# circuit.net
KiCad netlist of a schematic drawn in Altium Designer
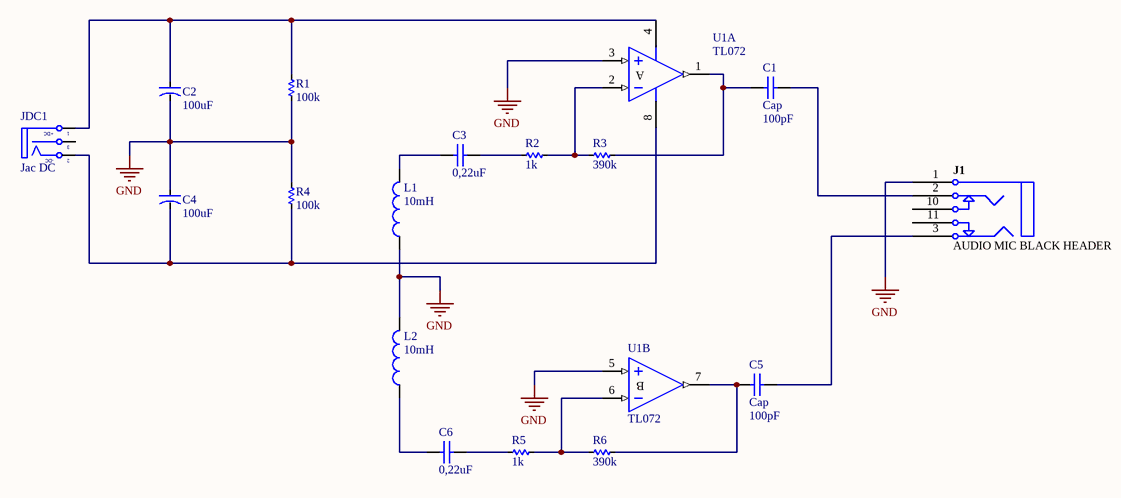
[diagram p0: circuit.schdoc]

(export (version "E")
  (design (tool "Eeschema 10.0.6"))
  (components
    (comp (ref "C1")
      (value "Cap")
      (footprint "RAD-0.3")
      (description "Capacitor")
      (fields (field (name "ALTIUM_VALUE") "100pF") (field (name "PUBLISHER") "Altium Limited"))
      (libsource (lib "Miscellaneous Devices") (part "Cap"))
    )
    (comp (ref "C2")
      (value "100uF")
      (footprint "CA-ALU-2.54")
      (description "Capacitor (Semiconductor SIM Model)")
      (fields (field (name "PUBLISHER") "Altium Limited"))
      (libsource (lib "Altium Library") (part "CN-ALU-DIP"))
    )
    (comp (ref "C3")
      (value "0,22uF")
      (footprint "RAD-0.3")
      (description "Capacitor")
      (fields (field (name "PUBLISHER") "Altium Limited"))
      (libsource (lib "Miscellaneous Devices") (part "Cap"))
    )
    (comp (ref "C4")
      (value "100uF")
      (footprint "CA-ALU-2.54")
      (description "Capacitor (Semiconductor SIM Model)")
      (fields (field (name "PUBLISHER") "Altium Limited"))
      (libsource (lib "Altium Library") (part "CN-ALU-DIP"))
    )
    (comp (ref "C5")
      (value "Cap")
      (footprint "RAD-0.3")
      (description "Capacitor")
      (fields (field (name "ALTIUM_VALUE") "100pF") (field (name "PUBLISHER") "Altium Limited"))
      (libsource (lib "Miscellaneous Devices") (part "Cap"))
    )
    (comp (ref "C6")
      (value "0,22uF")
      (footprint "RAD-0.3")
      (description "Capacitor")
      (fields (field (name "PUBLISHER") "Altium Limited"))
      (libsource (lib "Miscellaneous Devices") (part "Cap"))
    )
    (comp (ref "J1")
      (value "AUDIO MIC BLACK HEADER")
      (footprint "CON MIC1")
      (libsource (lib "Altium Library") (part "CON MIC1"))
    )
    (comp (ref "JDC1")
      (value "Jac DC")
      (footprint "DC0")
      (description "Jac DC input")
      (libsource (lib "Altium Library") (part "DCIN"))
    )
    (comp (ref "L1")
      (value "10mH")
      (footprint "0402-A")
      (description "Inductor")
      (fields (field (name "PUBLISHER") "Altium Limited"))
      (libsource (lib "Miscellaneous Devices") (part "Inductor"))
    )
    (comp (ref "L2")
      (value "10mH")
      (footprint "0402-A")
      (description "Inductor")
      (fields (field (name "PUBLISHER") "Altium Limited"))
      (libsource (lib "Miscellaneous Devices") (part "Inductor"))
    )
    (comp (ref "R1")
      (value "100k")
      (footprint "RES-1/4WD")
      (description "Res")
      (fields
        (field (name "MANUFACTURER") "Generic Components")
        (field (name "PUBLISHER") "Altium Hobart Technology Centre")
      )
      (libsource (lib "Altium Library") (part "Res"))
    )
    (comp (ref "R2")
      (value "1k")
      (footprint "RES-1/4WD")
      (description "Res")
      (fields
        (field (name "MANUFACTURER") "Generic Components")
        (field (name "PUBLISHER") "Altium Hobart Technology Centre")
      )
      (libsource (lib "Altium Library") (part "Res"))
    )
    (comp (ref "R3")
      (value "390k")
      (footprint "RES-1/4WD")
      (description "Res")
      (fields
        (field (name "MANUFACTURER") "Generic Components")
        (field (name "PUBLISHER") "Altium Hobart Technology Centre")
      )
      (libsource (lib "Altium Library") (part "Res"))
    )
    (comp (ref "R4")
      (value "100k")
      (footprint "RES-1/4WD")
      (description "Res")
      (fields
        (field (name "MANUFACTURER") "Generic Components")
        (field (name "PUBLISHER") "Altium Hobart Technology Centre")
      )
      (libsource (lib "Altium Library") (part "Res"))
    )
    (comp (ref "R5")
      (value "1k")
      (footprint "RES-1/4WD")
      (description "Res")
      (fields
        (field (name "MANUFACTURER") "Generic Components")
        (field (name "PUBLISHER") "Altium Hobart Technology Centre")
      )
      (libsource (lib "Altium Library") (part "Res"))
    )
    (comp (ref "R6")
      (value "390k")
      (footprint "RES-1/4WD")
      (description "Res")
      (fields
        (field (name "MANUFACTURER") "Generic Components")
        (field (name "PUBLISHER") "Altium Hobart Technology Centre")
      )
      (libsource (lib "Altium Library") (part "Res"))
    )
    (comp (ref "U1") (value "TL072") (footprint "DIP8") (libsource (lib "Altium Library") (part "TL072")))
  )
  (nets
    (net (code "1") (name "GND") (class "Default")
      (node (ref "C2") (pin "2") (pinfunction "2_2") (pintype "passive"))
      (node (ref "C4") (pin "1") (pinfunction "1_1") (pintype "passive"))
      (node (ref "J1") (pin "1") (pintype "passive"))
      (node (ref "L1") (pin "1") (pinfunction "1_1") (pintype "passive"))
      (node (ref "L2") (pin "2") (pinfunction "2_2") (pintype "passive"))
      (node (ref "R1") (pin "2") (pinfunction "2_2") (pintype "passive"))
      (node (ref "R4") (pin "2") (pinfunction "2_2") (pintype "passive"))
      (node (ref "U1") (pin "3") (pinfunction "IN+_3") (pintype "input"))
      (node (ref "U1") (pin "5") (pinfunction "IN+_5") (pintype "input"))
    )
    (net (code "2") (name "Net-(C1-Pad2)") (class "Default")
      (node (ref "C1") (pin "2") (pinfunction "2_2") (pintype "passive"))
      (node (ref "J1") (pin "2") (pintype "passive"))
    )
    (net (code "3") (name "Net-(C3-Pad1)") (class "Default")
      (node (ref "C3") (pin "1") (pinfunction "1_1") (pintype "passive"))
      (node (ref "L1") (pin "2") (pinfunction "2_2") (pintype "passive"))
    )
    (net (code "4") (name "Net-(C3-Pad2)") (class "Default")
      (node (ref "C3") (pin "2") (pinfunction "2_2") (pintype "passive"))
      (node (ref "R2") (pin "2") (pinfunction "2_2") (pintype "passive"))
    )
    (net (code "5") (name "Net-(C5-Pad2)") (class "Default")
      (node (ref "C5") (pin "2") (pinfunction "2_2") (pintype "passive"))
      (node (ref "J1") (pin "3") (pintype "passive"))
    )
    (net (code "6") (name "Net-(C6-Pad1)") (class "Default")
      (node (ref "C6") (pin "1") (pinfunction "1_1") (pintype "passive"))
      (node (ref "L2") (pin "1") (pinfunction "1_1") (pintype "passive"))
    )
    (net (code "7") (name "Net-(C6-Pad2)") (class "Default")
      (node (ref "C6") (pin "2") (pinfunction "2_2") (pintype "passive"))
      (node (ref "R5") (pin "2") (pinfunction "2_2") (pintype "passive"))
    )
    (net (code "8") (name "Net-(JDC1-T)") (class "Default")
      (node (ref "C2") (pin "1") (pinfunction "1_1") (pintype "passive"))
      (node (ref "JDC1") (pin "1") (pinfunction "T_1") (pintype "passive"))
      (node (ref "R1") (pin "1") (pinfunction "1_1") (pintype "passive"))
      (node (ref "U1") (pin "4") (pinfunction "V-_4") (pintype "power_in"))
    )
    (net (code "9") (name "Net-(JDC1-TN)") (class "Default")
      (node (ref "C4") (pin "2") (pinfunction "2_2") (pintype "passive"))
      (node (ref "JDC1") (pin "2") (pinfunction "TN_2") (pintype "passive"))
      (node (ref "R4") (pin "1") (pinfunction "1_1") (pintype "passive"))
      (node (ref "U1") (pin "8") (pinfunction "V+_8") (pintype "power_in"))
    )
    (net (code "10") (name "Net-(U1A-IN-)") (class "Default")
      (node (ref "R2") (pin "1") (pinfunction "1_1") (pintype "passive"))
      (node (ref "R3") (pin "2") (pinfunction "2_2") (pintype "passive"))
      (node (ref "U1") (pin "2") (pinfunction "IN-_2") (pintype "input"))
    )
    (net (code "11") (name "Net-(U1A-OUT)") (class "Default")
      (node (ref "C1") (pin "1") (pinfunction "1_1") (pintype "passive"))
      (node (ref "R3") (pin "1") (pinfunction "1_1") (pintype "passive"))
      (node (ref "U1") (pin "1") (pinfunction "OUT_1") (pintype "output"))
    )
    (net (code "12") (name "Net-(U1B-IN-)") (class "Default")
      (node (ref "R5") (pin "1") (pinfunction "1_1") (pintype "passive"))
      (node (ref "R6") (pin "2") (pinfunction "2_2") (pintype "passive"))
      (node (ref "U1") (pin "6") (pinfunction "IN-_6") (pintype "input"))
    )
    (net (code "13") (name "Net-(U1B-OUT)") (class "Default")
      (node (ref "C5") (pin "1") (pinfunction "1_1") (pintype "passive"))
      (node (ref "R6") (pin "1") (pinfunction "1_1") (pintype "passive"))
      (node (ref "U1") (pin "7") (pinfunction "OUT_7") (pintype "output"))
    )
    (net (code "14") (name "unconnected-(J1-Pad10)") (class "Default")
      (node (ref "J1") (pin "10") (pintype "passive"))
    )
    (net (code "15") (name "unconnected-(J1-Pad11)") (class "Default")
      (node (ref "J1") (pin "11") (pintype "passive"))
    )
    (net (code "16") (name "unconnected-(JDC1-S-Pad3)") (class "Default")
      (node (ref "JDC1") (pin "3") (pinfunction "S_3") (pintype "power_in"))
    )
  )
)
